# SH9_-_RS-485.net
KiCad netlist of a schematic drawn in Altium Designer
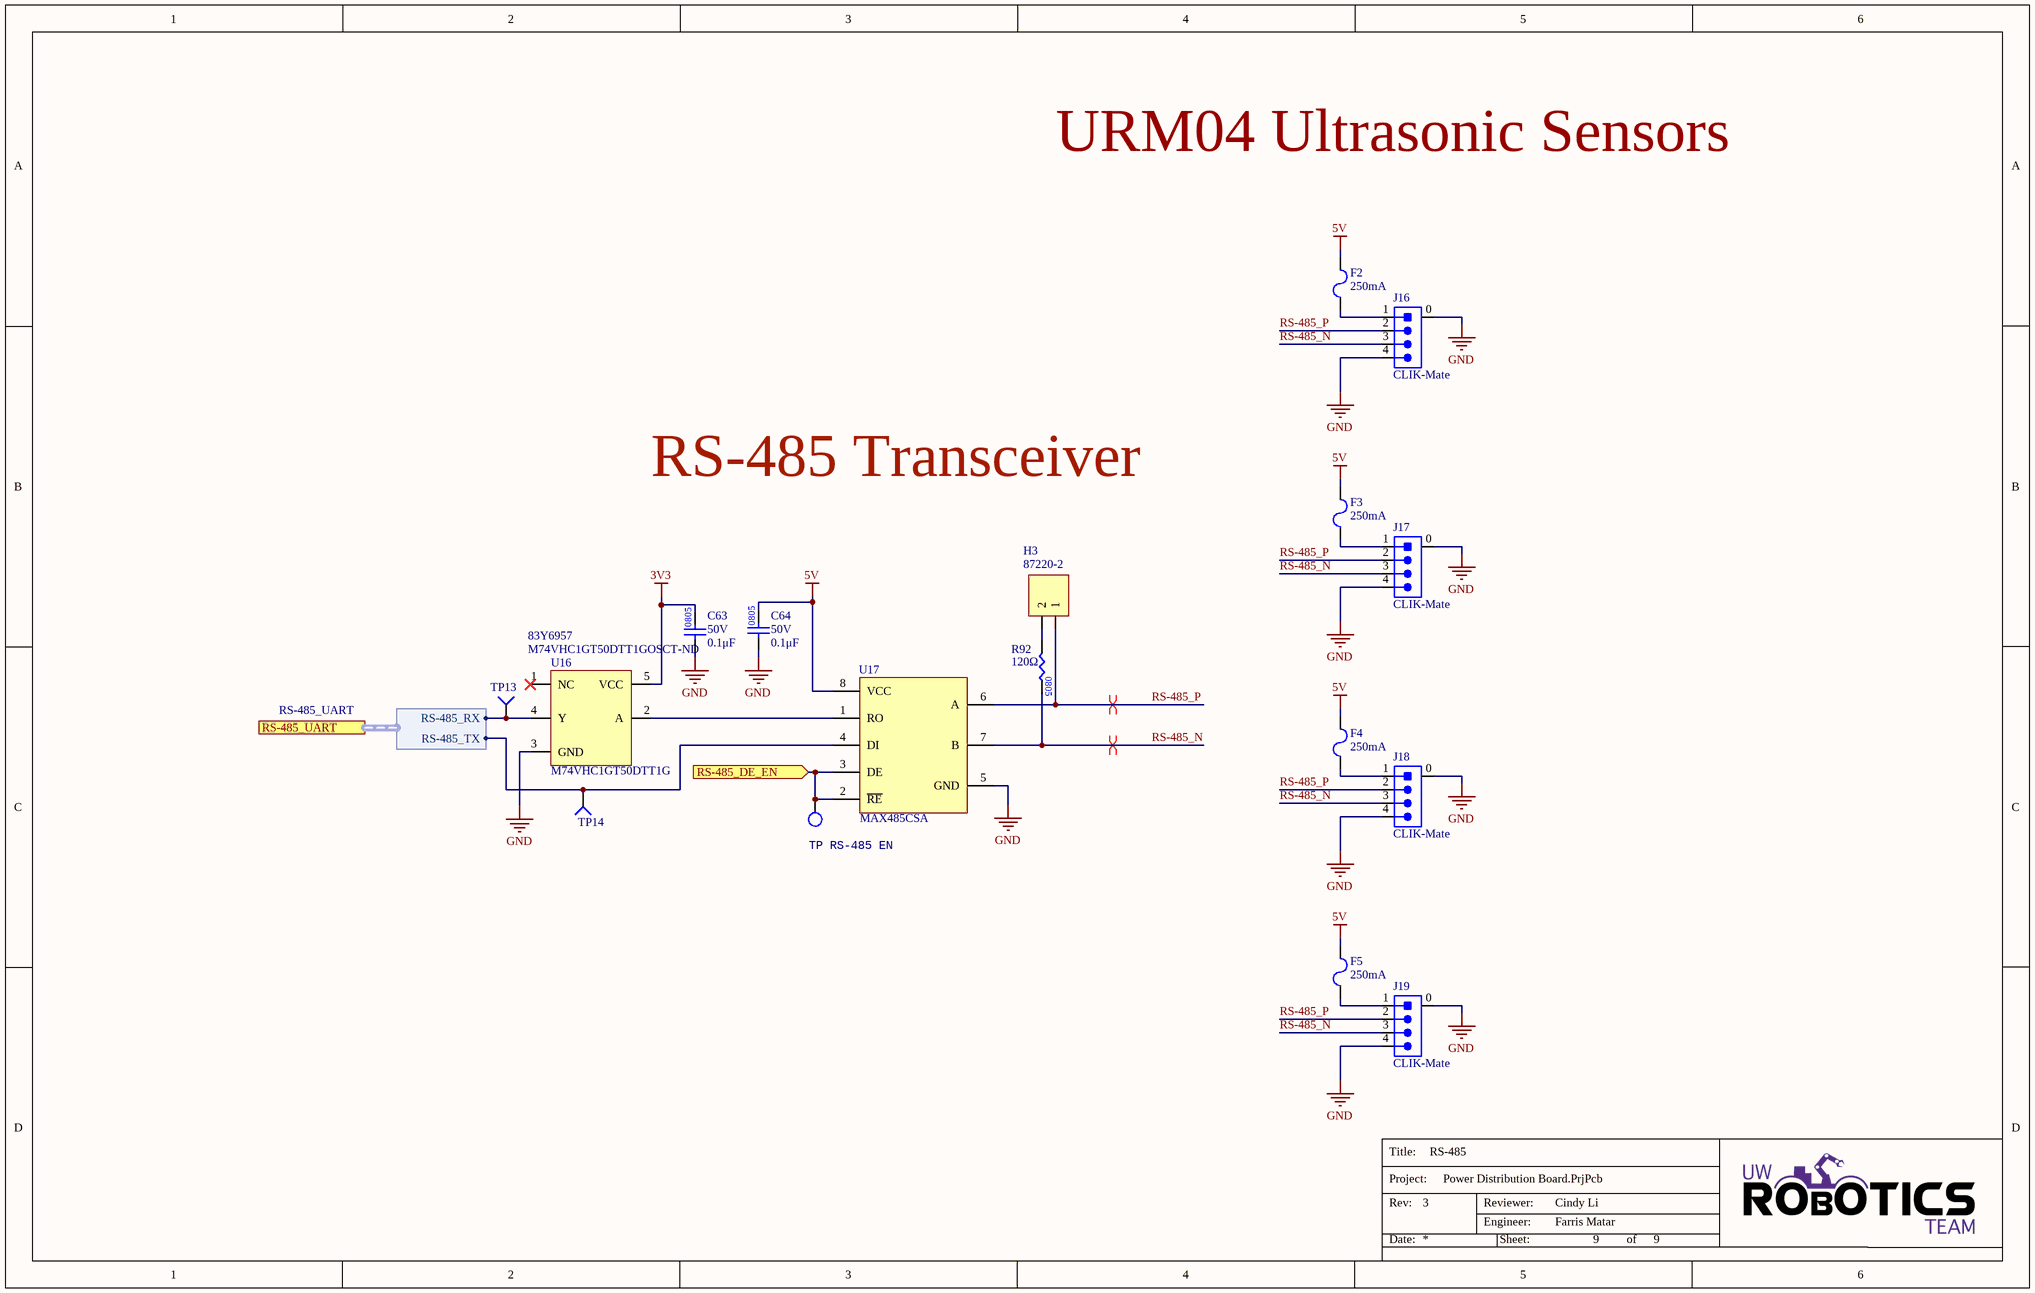
[diagram p0: SH9 - RS-485.SchDoc]

(export (version "E")
  (design (tool "Eeschema 10.0.6"))
  (components
    (comp (ref "C63")
      (value "0.1μF")
      (footprint "CAP2012")
      (description "CAP CER 0.1UF 50V X7R 0805")
      (fields
        (field (name "VOLTAGE RATING") "50V")
        (field (name "LCSC PART #") "C49678")
        (field (name "Comment") "CAP_0.1uF_50V_0805")
      )
      (libsource (lib "UWRT_Schematic_Library_2020") (part "CAP_0.1uF_50V_0805"))
    )
    (comp (ref "C64")
      (value "0.1μF")
      (footprint "CAP2012")
      (description "CAP CER 0.1UF 50V X7R 0805")
      (fields
        (field (name "VOLTAGE RATING") "50V")
        (field (name "LCSC PART #") "C49678")
        (field (name "Comment") "CAP_0.1uF_50V_0805")
      )
      (libsource (lib "UWRT_Schematic_Library_2020") (part "CAP_0.1uF_50V_0805"))
    )
    (comp (ref "F2")
      (value "FUSE_250mA_1206")
      (footprint "FUSE_1206")
      (description "FUSE BOARD MNT 250MA 125VAC/VDC")
      (fields (field (name "CURRENT RATING") "250mA"))
      (libsource (lib "UWRT_Schematic_Library_2020") (part "FUSE_250mA_1206"))
    )
    (comp (ref "F3")
      (value "FUSE_250mA_1206")
      (footprint "FUSE_1206")
      (description "FUSE BOARD MNT 250MA 125VAC/VDC")
      (fields (field (name "CURRENT RATING") "250mA"))
      (libsource (lib "UWRT_Schematic_Library_2020") (part "FUSE_250mA_1206"))
    )
    (comp (ref "F4")
      (value "FUSE_250mA_1206")
      (footprint "FUSE_1206")
      (description "FUSE BOARD MNT 250MA 125VAC/VDC")
      (fields (field (name "CURRENT RATING") "250mA"))
      (libsource (lib "UWRT_Schematic_Library_2020") (part "FUSE_250mA_1206"))
    )
    (comp (ref "F5")
      (value "FUSE_250mA_1206")
      (footprint "FUSE_1206")
      (description "FUSE BOARD MNT 250MA 125VAC/VDC")
      (fields (field (name "CURRENT RATING") "250mA"))
      (libsource (lib "UWRT_Schematic_Library_2020") (part "FUSE_250mA_1206"))
    )
    (comp (ref "H3")
      (value "JUMPER_2")
      (footprint "HDR1X2")
      (description "HEADER 2X1")
      (fields (field (name "MANUFACTURER PART NUMBER 1") "87220-2"))
      (libsource (lib "UWRT_Schematic_Library_2020") (part "JUMPER_2"))
    )
    (comp (ref "J16")
      (value "CON_4M_SM_RA")
      (footprint "MOLEX-5025850470")
      (description "CONN HEADER SMD RIGHT ANGLE 1.5 MM PITCH")
      (fields (field (name "FAMILY") "CLIK-Mate"))
      (libsource (lib "UWRT_Schematic_Library_2020") (part "CON_4M_SM_RA"))
    )
    (comp (ref "J17")
      (value "CON_4M_SM_RA")
      (footprint "MOLEX-5025850470")
      (description "CONN HEADER SMD RIGHT ANGLE 1.5 MM PITCH")
      (fields (field (name "FAMILY") "CLIK-Mate"))
      (libsource (lib "UWRT_Schematic_Library_2020") (part "CON_4M_SM_RA"))
    )
    (comp (ref "J18")
      (value "CON_4M_SM_RA")
      (footprint "MOLEX-5025850470")
      (description "CONN HEADER SMD RIGHT ANGLE 1.5 MM PITCH")
      (fields (field (name "FAMILY") "CLIK-Mate"))
      (libsource (lib "UWRT_Schematic_Library_2020") (part "CON_4M_SM_RA"))
    )
    (comp (ref "J19")
      (value "CON_4M_SM_RA")
      (footprint "MOLEX-5025850470")
      (description "CONN HEADER SMD RIGHT ANGLE 1.5 MM PITCH")
      (fields (field (name "FAMILY") "CLIK-Mate"))
      (libsource (lib "UWRT_Schematic_Library_2020") (part "CON_4M_SM_RA"))
    )
    (comp (ref "R92")
      (value "120Ω")
      (footprint "RES0805")
      (description "RES 120 OHM 1% 1/8W 0805")
      (fields (field (name "LCSC PART #") "C17437") (field (name "Comment") "RES_120Ω_0805_1%"))
      (libsource (lib "UWRT_Schematic_Library_2020") (part "RES_120Ω_0805_1%"))
    )
    (comp (ref "TP RS-485 EN")
      (value "TESTPOINT_LOOP")
      (footprint "TESTPOINT_LOOP")
      (description "TESTPOINT THRUHOLE")
      (libsource (lib "UWRT_Schematic_Library_2020") (part "TESTPOINT_LOOP"))
    )
    (comp (ref "TP13")
      (value "TESTPOINT_1MM_CIRCLE")
      (footprint "TESTPOINT_CIRCLE_1MM")
      (description "TESTPOINT 1MM CIRCLE")
      (libsource (lib "UWRT_Schematic_Library_2020") (part "TESTPOINT_1MM_CIRCLE"))
    )
    (comp (ref "TP14")
      (value "TESTPOINT_1MM_CIRCLE")
      (footprint "TESTPOINT_CIRCLE_1MM")
      (description "TESTPOINT 1MM CIRCLE")
      (libsource (lib "UWRT_Schematic_Library_2020") (part "TESTPOINT_1MM_CIRCLE"))
    )
    (comp (ref "U16")
      (value "IC_BUFFER")
      (footprint "SOT23-5")
      (description "IC BUFFER NON-INVERT 5.5V 5TSOP")
      (fields
        (field (name "MANUFACTURER PART NUMBER 1") "M74VHC1GT50DTT1G")
        (field (name "SUPPLIER PART NUMBER 1") "M74VHC1GT50DTT1GOSCT-ND")
        (field (name "SUPPLIER PART NUMBER 2") "83Y6957")
      )
      (libsource (lib "UWRT_Schematic_Library_2020") (part "IC_BUFFER"))
    )
    (comp (ref "U17")
      (value "MAX485CSA")
      (footprint "SOIC127P600X175-8N")
      (description "IC RS485 TRANSCEIVER HALF 1/1 8SOIC")
      (fields (field (name "LCSC PART #") "C9945"))
      (libsource (lib "UWRT_Schematic_Library_2020") (part "MAX485CSA"))
    )
  )
  (nets
    (net (code "2") (name "/RS-485_DE_EN") (class "Default")
      (node (ref "TP RS-485 EN") (pin "1") (pintype "passive"))
      (node (ref "U17") (pin "2") (pinfunction "~{RE}_2") (pintype "passive"))
      (node (ref "U17") (pin "3") (pinfunction "DE_3") (pintype "passive"))
    )
    (net (code "3") (name "/RS-485_N") (class "Default")
      (node (ref "J16") (pin "3") (pinfunction "3_3") (pintype "passive"))
      (node (ref "J17") (pin "3") (pinfunction "3_3") (pintype "passive"))
      (node (ref "J18") (pin "3") (pinfunction "3_3") (pintype "passive"))
      (node (ref "J19") (pin "3") (pinfunction "3_3") (pintype "passive"))
      (node (ref "R92") (pin "2") (pinfunction "2_2") (pintype "passive"))
      (node (ref "U17") (pin "7") (pinfunction "B_7") (pintype "passive"))
    )
    (net (code "4") (name "/RS-485_P") (class "Default")
      (node (ref "H3") (pin "1") (pinfunction "1_1") (pintype "passive"))
      (node (ref "J16") (pin "2") (pinfunction "2_2") (pintype "passive"))
      (node (ref "J17") (pin "2") (pinfunction "2_2") (pintype "passive"))
      (node (ref "J18") (pin "2") (pinfunction "2_2") (pintype "passive"))
      (node (ref "J19") (pin "2") (pinfunction "2_2") (pintype "passive"))
      (node (ref "U17") (pin "6") (pinfunction "A_6") (pintype "passive"))
    )
    (net (code "6") (name "3V3") (class "Default")
      (node (ref "C63") (pin "2") (pinfunction "2_2") (pintype "passive"))
      (node (ref "U16") (pin "5") (pinfunction "VCC_5") (pintype "passive"))
    )
    (net (code "7") (name "5V") (class "Default")
      (node (ref "C64") (pin "2") (pinfunction "2_2") (pintype "passive"))
      (node (ref "F2") (pin "2") (pinfunction "2_2") (pintype "passive"))
      (node (ref "F3") (pin "2") (pinfunction "2_2") (pintype "passive"))
      (node (ref "F4") (pin "2") (pinfunction "2_2") (pintype "passive"))
      (node (ref "F5") (pin "2") (pinfunction "2_2") (pintype "passive"))
      (node (ref "U17") (pin "8") (pinfunction "VCC_8") (pintype "power_in"))
    )
    (net (code "8") (name "GND") (class "Default")
      (node (ref "C63") (pin "1") (pinfunction "1_1") (pintype "passive"))
      (node (ref "C64") (pin "1") (pinfunction "1_1") (pintype "passive"))
      (node (ref "J16") (pin "0") (pinfunction "0_0") (pintype "passive"))
      (node (ref "J16") (pin "4") (pinfunction "4_4") (pintype "passive"))
      (node (ref "J17") (pin "0") (pinfunction "0_0") (pintype "passive"))
      (node (ref "J17") (pin "4") (pinfunction "4_4") (pintype "passive"))
      (node (ref "J18") (pin "0") (pinfunction "0_0") (pintype "passive"))
      (node (ref "J18") (pin "4") (pinfunction "4_4") (pintype "passive"))
      (node (ref "J19") (pin "0") (pinfunction "0_0") (pintype "passive"))
      (node (ref "J19") (pin "4") (pinfunction "4_4") (pintype "passive"))
      (node (ref "U16") (pin "3") (pinfunction "GND_3") (pintype "passive"))
      (node (ref "U17") (pin "5") (pinfunction "GND_5") (pintype "power_in"))
    )
    (net (code "9") (name "Net-(F2-Pad1)") (class "Default")
      (node (ref "F2") (pin "1") (pinfunction "1_1") (pintype "passive"))
      (node (ref "J16") (pin "1") (pinfunction "1_1") (pintype "passive"))
    )
    (net (code "10") (name "Net-(F3-Pad1)") (class "Default")
      (node (ref "F3") (pin "1") (pinfunction "1_1") (pintype "passive"))
      (node (ref "J17") (pin "1") (pinfunction "1_1") (pintype "passive"))
    )
    (net (code "11") (name "Net-(F4-Pad1)") (class "Default")
      (node (ref "F4") (pin "1") (pinfunction "1_1") (pintype "passive"))
      (node (ref "J18") (pin "1") (pinfunction "1_1") (pintype "passive"))
    )
    (net (code "12") (name "Net-(F5-Pad1)") (class "Default")
      (node (ref "F5") (pin "1") (pinfunction "1_1") (pintype "passive"))
      (node (ref "J19") (pin "1") (pinfunction "1_1") (pintype "passive"))
    )
    (net (code "13") (name "Net-(H3-Pad2)") (class "Default")
      (node (ref "H3") (pin "2") (pinfunction "2_2") (pintype "passive"))
      (node (ref "R92") (pin "1") (pinfunction "1_1") (pintype "passive"))
    )
    (net (code "14") (name "Net-(TP13-=value)") (class "Default")
      (node (ref "TP13") (pin "1") (pinfunction "=value_1") (pintype "passive"))
      (node (ref "U16") (pin "4") (pinfunction "Y_4") (pintype "passive"))
    )
    (net (code "15") (name "Net-(TP14-=value)") (class "Default")
      (node (ref "TP14") (pin "1") (pinfunction "=value_1") (pintype "passive"))
      (node (ref "U17") (pin "4") (pinfunction "DI_4") (pintype "passive"))
    )
    (net (code "16") (name "Net-(U16-A)") (class "Default")
      (node (ref "U16") (pin "2") (pinfunction "A_2") (pintype "passive"))
      (node (ref "U17") (pin "1") (pinfunction "RO_1") (pintype "passive"))
    )
    (net (code "17") (name "unconnected-(U16-NC-Pad1)") (class "Default")
      (node (ref "U16") (pin "1") (pinfunction "NC_1") (pintype "passive+no_connect"))
    )
  )
)
